# Microcontroller.net
KiCad netlist of a schematic drawn in Altium Designer
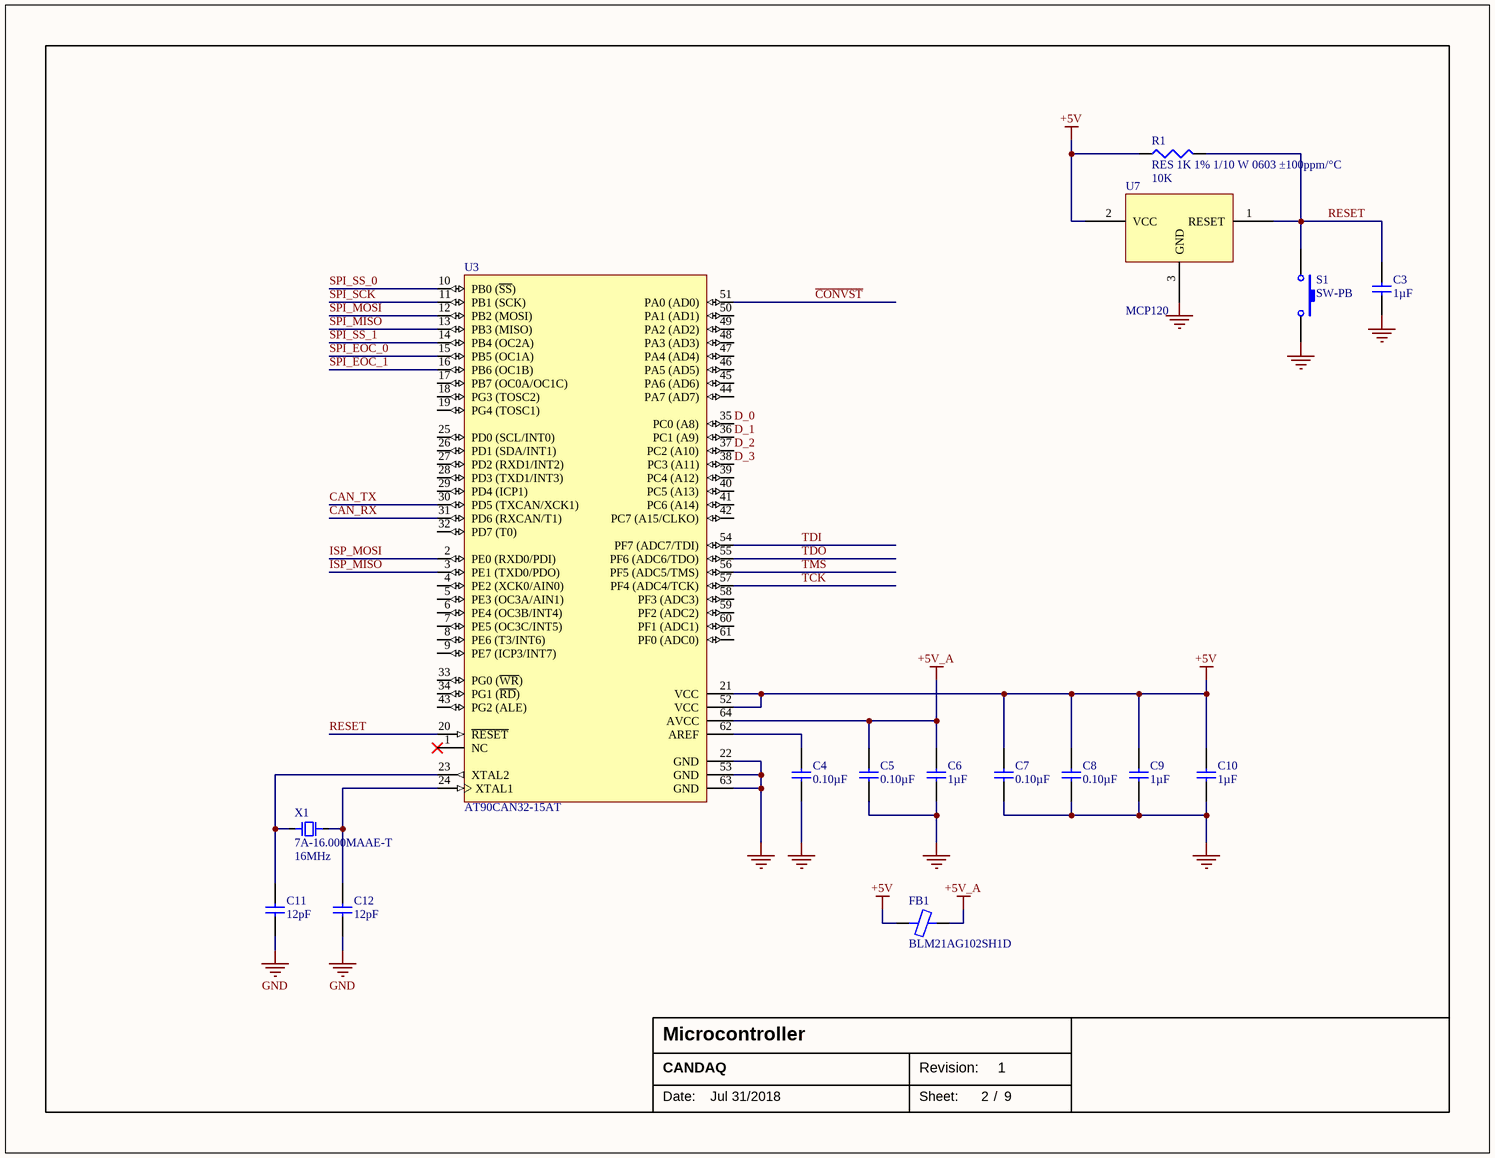
[diagram p0: Microcontroller.SchDoc]

(export (version "E")
  (design (tool "Eeschema 10.0.6"))
  (components
    (comp (ref "C3")
      (value "1µF")
      (footprint "1206")
      (fields
        (field (name "PART NUMBER") "CC0805KKX7R7BB105")
        (field (name "TOLERANCE") "±10%")
        (field (name "VOLTAGE") "16V")
      )
      (libsource (lib "Capacitors") (part "Capacitor"))
    )
    (comp (ref "C4")
      (value "0.10µF")
      (footprint "1206")
      (fields
        (field (name "PART NUMBER") "CC0402KRX7R7BB104")
        (field (name "TOLERANCE") "±10%")
        (field (name "VOLTAGE") "16V")
      )
      (libsource (lib "Capacitors") (part "Capacitor"))
    )
    (comp (ref "C5")
      (value "0.10µF")
      (footprint "1206")
      (fields
        (field (name "PART NUMBER") "CC0402KRX7R7BB104")
        (field (name "TOLERANCE") "±10%")
        (field (name "VOLTAGE") "16V")
      )
      (libsource (lib "Capacitors") (part "Capacitor"))
    )
    (comp (ref "C6")
      (value "1µF")
      (footprint "1206")
      (fields
        (field (name "PART NUMBER") "CC0805KKX7R7BB105")
        (field (name "TOLERANCE") "±10%")
        (field (name "VOLTAGE") "16V")
      )
      (libsource (lib "Capacitors") (part "Capacitor"))
    )
    (comp (ref "C7")
      (value "0.10µF")
      (footprint "1206")
      (fields
        (field (name "PART NUMBER") "CC0402KRX7R7BB104")
        (field (name "TOLERANCE") "±10%")
        (field (name "VOLTAGE") "16V")
      )
      (libsource (lib "Capacitors") (part "Capacitor"))
    )
    (comp (ref "C8")
      (value "0.10µF")
      (footprint "1206")
      (fields
        (field (name "PART NUMBER") "CC0402KRX7R7BB104")
        (field (name "TOLERANCE") "±10%")
        (field (name "VOLTAGE") "16V")
      )
      (libsource (lib "Capacitors") (part "Capacitor"))
    )
    (comp (ref "C9")
      (value "1µF")
      (footprint "1206")
      (fields
        (field (name "PART NUMBER") "CC0805KKX7R7BB105")
        (field (name "TOLERANCE") "±10%")
        (field (name "VOLTAGE") "16V")
      )
      (libsource (lib "Capacitors") (part "Capacitor"))
    )
    (comp (ref "C10")
      (value "1µF")
      (footprint "1206")
      (fields
        (field (name "PART NUMBER") "CC0805KKX7R7BB105")
        (field (name "TOLERANCE") "±10%")
        (field (name "VOLTAGE") "16V")
      )
      (libsource (lib "Capacitors") (part "Capacitor"))
    )
    (comp (ref "C11")
      (value "12pF")
      (footprint "1206")
      (fields
        (field (name "PART NUMBER") "CC0402JRNPO9BN120")
        (field (name "TOLERANCE") "±5%")
        (field (name "VOLTAGE") "50V")
      )
      (libsource (lib "Capacitors") (part "Capacitor"))
    )
    (comp (ref "C12")
      (value "12pF")
      (footprint "1206")
      (fields
        (field (name "PART NUMBER") "CC0402JRNPO9BN120")
        (field (name "TOLERANCE") "±5%")
        (field (name "VOLTAGE") "50V")
      )
      (libsource (lib "Capacitors") (part "Capacitor"))
    )
    (comp (ref "FB1")
      (value "BLM21AG102SH1D")
      (footprint "INDC2012X11N")
      (libsource (lib "PDU-UV17") (part "BLM21AG102SH1D"))
    )
    (comp (ref "R1")
      (value "RES 1K 1% 1/10 W 0603 ±100ppm/°C")
      (footprint "1206")
      (description "Resistor")
      (fields (field (name "ALTIUM_VALUE") "10K") (field (name "PUBLISHER") "Altium Limited"))
      (libsource (lib "Miscellaneous Devices") (part "Res3"))
    )
    (comp (ref "S1")
      (value "SW-PB")
      (footprint "Switch")
      (description "Switch")
      (fields (field (name "PUBLISHER") "Altium Limited"))
      (libsource (lib "Miscellaneous Devices") (part "SW-PB"))
    )
    (comp (ref "U3")
      (value "AT90CAN32-15AT")
      (footprint "TQFP80P1600X1600X120-64N")
      (libsource (lib "PDU-UV17") (part "AT90CAN32-15AT"))
    )
    (comp (ref "U7") (value "MCP120") (footprint "MCP120") (libsource (lib "CANDAQ") (part "MCP120")))
    (comp (ref "X1")
      (value "7A-16.000MAAE-T")
      (footprint "QFN200P500X320X135-2N")
      (description "SMD Crystal Oscillator 12 pF")
      (fields (field (name "ALTIUM_VALUE") "16MHz"))
      (libsource (lib "PDUv2") (part "7A-16.000MAAE-T"))
    )
  )
  (nets
    (net (code "1") (name "+5V") (class "Default")
      (node (ref "C10") (pin "1") (pinfunction "1_1") (pintype "passive"))
      (node (ref "C7") (pin "2") (pinfunction "2_2") (pintype "passive"))
      (node (ref "C8") (pin "2") (pinfunction "2_2") (pintype "passive"))
      (node (ref "C9") (pin "1") (pinfunction "1_1") (pintype "passive"))
      (node (ref "FB1") (pin "1") (pinfunction "1_1") (pintype "passive"))
      (node (ref "R1") (pin "1") (pinfunction "1_1") (pintype "passive"))
      (node (ref "U3") (pin "21") (pinfunction "VCC_21") (pintype "power_in"))
      (node (ref "U3") (pin "52") (pinfunction "VCC_52") (pintype "power_in"))
      (node (ref "U7") (pin "2") (pinfunction "VCC_2") (pintype "passive"))
    )
    (net (code "2") (name "+5V_A") (class "Default")
      (node (ref "C5") (pin "2") (pinfunction "2_2") (pintype "passive"))
      (node (ref "C6") (pin "1") (pinfunction "1_1") (pintype "passive"))
      (node (ref "FB1") (pin "2") (pinfunction "2_2") (pintype "passive"))
      (node (ref "U3") (pin "64") (pinfunction "AVCC_64") (pintype "power_in"))
    )
    (net (code "3") (name "/CAN_RX") (class "Default")
      (node (ref "U3") (pin "31") (pinfunction "PD6_(RXCAN/T1)_31") (pintype "bidirectional"))
    )
    (net (code "4") (name "/CAN_TX") (class "Default")
      (node (ref "U3") (pin "30") (pinfunction "PD5_(TXCAN/XCK1)_30") (pintype "bidirectional"))
    )
    (net (code "5") (name "/D_0") (class "Default")
      (node (ref "U3") (pin "35") (pinfunction "PC0_(A8)_35") (pintype "bidirectional"))
    )
    (net (code "6") (name "/D_1") (class "Default")
      (node (ref "U3") (pin "36") (pinfunction "PC1_(A9)_36") (pintype "bidirectional"))
    )
    (net (code "7") (name "/D_2") (class "Default")
      (node (ref "U3") (pin "37") (pinfunction "PC2_(A10)_37") (pintype "bidirectional"))
    )
    (net (code "8") (name "/D_3") (class "Default")
      (node (ref "U3") (pin "38") (pinfunction "PC3_(A11)_38") (pintype "bidirectional"))
    )
    (net (code "9") (name "/ISP_MISO") (class "Default")
      (node (ref "U3") (pin "3") (pinfunction "PE1_(TXD0/PDO)_3") (pintype "bidirectional"))
    )
    (net (code "10") (name "/ISP_MOSI") (class "Default")
      (node (ref "U3") (pin "2") (pinfunction "PE0_(RXD0/PDI)_2") (pintype "bidirectional"))
    )
    (net (code "11") (name "/RESET") (class "Default")
      (node (ref "C3") (pin "1") (pinfunction "1_1") (pintype "passive"))
      (node (ref "R1") (pin "2") (pinfunction "2_2") (pintype "passive"))
      (node (ref "S1") (pin "1") (pinfunction "1_1") (pintype "passive"))
      (node (ref "U3") (pin "20") (pinfunction "~{RESET}_20") (pintype "input"))
      (node (ref "U7") (pin "1") (pinfunction "RESET_1") (pintype "passive"))
    )
    (net (code "12") (name "/SPI_EOC_0") (class "Default")
      (node (ref "U3") (pin "15") (pinfunction "PB5_(OC1A)_15") (pintype "bidirectional"))
    )
    (net (code "13") (name "/SPI_EOC_1") (class "Default")
      (node (ref "U3") (pin "16") (pinfunction "PB6_(OC1B)_16") (pintype "bidirectional"))
    )
    (net (code "14") (name "/SPI_MISO") (class "Default")
      (node (ref "U3") (pin "13") (pinfunction "PB3_(MISO)_13") (pintype "bidirectional"))
    )
    (net (code "15") (name "/SPI_MOSI") (class "Default")
      (node (ref "U3") (pin "12") (pinfunction "PB2_(MOSI)_12") (pintype "bidirectional"))
    )
    (net (code "16") (name "/SPI_SCK") (class "Default")
      (node (ref "U3") (pin "11") (pinfunction "PB1_(SCK)_11") (pintype "bidirectional"))
    )
    (net (code "17") (name "/SPI_SS_0") (class "Default")
      (node (ref "U3") (pin "10") (pinfunction "PB0_(~{SS})_10") (pintype "bidirectional"))
    )
    (net (code "18") (name "/SPI_SS_1") (class "Default")
      (node (ref "U3") (pin "14") (pinfunction "PB4_(OC2A)_14") (pintype "bidirectional"))
    )
    (net (code "19") (name "/TCK") (class "Default")
      (node (ref "U3") (pin "57") (pinfunction "PF4_(ADC4/TCK)_57") (pintype "bidirectional"))
    )
    (net (code "20") (name "/TDI") (class "Default")
      (node (ref "U3") (pin "54") (pinfunction "PF7_(ADC7/TDI)_54") (pintype "bidirectional"))
    )
    (net (code "21") (name "/TDO") (class "Default")
      (node (ref "U3") (pin "55") (pinfunction "PF6_(ADC6/TDO)_55") (pintype "bidirectional"))
    )
    (net (code "22") (name "/TMS") (class "Default")
      (node (ref "U3") (pin "56") (pinfunction "PF5_(ADC5/TMS)_56") (pintype "bidirectional"))
    )
    (net (code "23") (name "/~{CONVST}") (class "Default")
      (node (ref "U3") (pin "51") (pinfunction "PA0_(AD0)_51") (pintype "bidirectional"))
    )
    (net (code "24") (name "GND") (class "Default")
      (node (ref "C10") (pin "2") (pinfunction "2_2") (pintype "passive"))
      (node (ref "C11") (pin "1") (pinfunction "1_1") (pintype "passive"))
      (node (ref "C12") (pin "1") (pinfunction "1_1") (pintype "passive"))
      (node (ref "C3") (pin "2") (pinfunction "2_2") (pintype "passive"))
      (node (ref "C4") (pin "1") (pinfunction "1_1") (pintype "passive"))
      (node (ref "C5") (pin "1") (pinfunction "1_1") (pintype "passive"))
      (node (ref "C6") (pin "2") (pinfunction "2_2") (pintype "passive"))
      (node (ref "C7") (pin "1") (pinfunction "1_1") (pintype "passive"))
      (node (ref "C8") (pin "1") (pinfunction "1_1") (pintype "passive"))
      (node (ref "C9") (pin "2") (pinfunction "2_2") (pintype "passive"))
      (node (ref "S1") (pin "2") (pinfunction "2_2") (pintype "passive"))
      (node (ref "U3") (pin "22") (pinfunction "GND_22") (pintype "power_in"))
      (node (ref "U3") (pin "53") (pinfunction "GND_53") (pintype "power_in"))
      (node (ref "U3") (pin "63") (pinfunction "GND_63") (pintype "power_in"))
      (node (ref "U7") (pin "3") (pinfunction "GND_3") (pintype "passive"))
    )
    (net (code "25") (name "Net-(U3-AREF)") (class "Default")
      (node (ref "C4") (pin "2") (pinfunction "2_2") (pintype "passive"))
      (node (ref "U3") (pin "62") (pinfunction "AREF_62") (pintype "power_in"))
    )
    (net (code "26") (name "Net-(U3-XTAL1)") (class "Default")
      (node (ref "C12") (pin "2") (pinfunction "2_2") (pintype "passive"))
      (node (ref "U3") (pin "24") (pinfunction "XTAL1_24") (pintype "input"))
      (node (ref "X1") (pin "2") (pinfunction "2_2") (pintype "passive"))
    )
    (net (code "27") (name "Net-(U3-XTAL2)") (class "Default")
      (node (ref "C11") (pin "2") (pinfunction "2_2") (pintype "passive"))
      (node (ref "U3") (pin "23") (pinfunction "XTAL2_23") (pintype "output"))
      (node (ref "X1") (pin "1") (pinfunction "1_1") (pintype "passive"))
    )
    (net (code "28") (name "unconnected-(U3-NC-Pad1)") (class "Default")
      (node (ref "U3") (pin "1") (pinfunction "NC_1") (pintype "passive+no_connect"))
    )
    (net (code "29") (name "unconnected-(U3-PA1_(AD1)-Pad50)") (class "Default")
      (node (ref "U3") (pin "50") (pinfunction "PA1_(AD1)_50") (pintype "bidirectional"))
    )
    (net (code "30") (name "unconnected-(U3-PA2_(AD2)-Pad49)") (class "Default")
      (node (ref "U3") (pin "49") (pinfunction "PA2_(AD2)_49") (pintype "bidirectional"))
    )
    (net (code "31") (name "unconnected-(U3-PA3_(AD3)-Pad48)") (class "Default")
      (node (ref "U3") (pin "48") (pinfunction "PA3_(AD3)_48") (pintype "bidirectional"))
    )
    (net (code "32") (name "unconnected-(U3-PA4_(AD4)-Pad47)") (class "Default")
      (node (ref "U3") (pin "47") (pinfunction "PA4_(AD4)_47") (pintype "bidirectional"))
    )
    (net (code "33") (name "unconnected-(U3-PA5_(AD5)-Pad46)") (class "Default")
      (node (ref "U3") (pin "46") (pinfunction "PA5_(AD5)_46") (pintype "bidirectional"))
    )
    (net (code "34") (name "unconnected-(U3-PA6_(AD6)-Pad45)") (class "Default")
      (node (ref "U3") (pin "45") (pinfunction "PA6_(AD6)_45") (pintype "bidirectional"))
    )
    (net (code "35") (name "unconnected-(U3-PA7_(AD7)-Pad44)") (class "Default")
      (node (ref "U3") (pin "44") (pinfunction "PA7_(AD7)_44") (pintype "bidirectional"))
    )
    (net (code "36") (name "unconnected-(U3-PB7_(OC0A{slash}OC1C)-Pad17)") (class "Default")
      (node (ref "U3") (pin "17") (pinfunction "PB7_(OC0A/OC1C)_17") (pintype "bidirectional"))
    )
    (net (code "37") (name "unconnected-(U3-PC4_(A12)-Pad39)") (class "Default")
      (node (ref "U3") (pin "39") (pinfunction "PC4_(A12)_39") (pintype "bidirectional"))
    )
    (net (code "38") (name "unconnected-(U3-PC5_(A13)-Pad40)") (class "Default")
      (node (ref "U3") (pin "40") (pinfunction "PC5_(A13)_40") (pintype "bidirectional"))
    )
    (net (code "39") (name "unconnected-(U3-PC6_(A14)-Pad41)") (class "Default")
      (node (ref "U3") (pin "41") (pinfunction "PC6_(A14)_41") (pintype "bidirectional"))
    )
    (net (code "40") (name "unconnected-(U3-PC7_(A15{slash}CLKO)-Pad42)") (class "Default")
      (node (ref "U3") (pin "42") (pinfunction "PC7_(A15/CLKO)_42") (pintype "bidirectional"))
    )
    (net (code "41") (name "unconnected-(U3-PD0_(SCL{slash}INT0)-Pad25)") (class "Default")
      (node (ref "U3") (pin "25") (pinfunction "PD0_(SCL/INT0)_25") (pintype "bidirectional"))
    )
    (net (code "42") (name "unconnected-(U3-PD1_(SDA{slash}INT1)-Pad26)") (class "Default")
      (node (ref "U3") (pin "26") (pinfunction "PD1_(SDA/INT1)_26") (pintype "bidirectional"))
    )
    (net (code "43") (name "unconnected-(U3-PD2_(RXD1{slash}INT2)-Pad27)") (class "Default")
      (node (ref "U3") (pin "27") (pinfunction "PD2_(RXD1/INT2)_27") (pintype "bidirectional"))
    )
    (net (code "44") (name "unconnected-(U3-PD3_(TXD1{slash}INT3)-Pad28)") (class "Default")
      (node (ref "U3") (pin "28") (pinfunction "PD3_(TXD1/INT3)_28") (pintype "bidirectional"))
    )
    (net (code "45") (name "unconnected-(U3-PD4_(ICP1)-Pad29)") (class "Default")
      (node (ref "U3") (pin "29") (pinfunction "PD4_(ICP1)_29") (pintype "bidirectional"))
    )
    (net (code "46") (name "unconnected-(U3-PD7_(T0)-Pad32)") (class "Default")
      (node (ref "U3") (pin "32") (pinfunction "PD7_(T0)_32") (pintype "bidirectional"))
    )
    (net (code "47") (name "unconnected-(U3-PE2_(XCK0{slash}AIN0)-Pad4)") (class "Default")
      (node (ref "U3") (pin "4") (pinfunction "PE2_(XCK0/AIN0)_4") (pintype "bidirectional"))
    )
    (net (code "48") (name "unconnected-(U3-PE3_(OC3A{slash}AIN1)-Pad5)") (class "Default")
      (node (ref "U3") (pin "5") (pinfunction "PE3_(OC3A/AIN1)_5") (pintype "bidirectional"))
    )
    (net (code "49") (name "unconnected-(U3-PE4_(OC3B{slash}INT4)-Pad6)") (class "Default")
      (node (ref "U3") (pin "6") (pinfunction "PE4_(OC3B/INT4)_6") (pintype "bidirectional"))
    )
    (net (code "50") (name "unconnected-(U3-PE5_(OC3C{slash}INT5)-Pad7)") (class "Default")
      (node (ref "U3") (pin "7") (pinfunction "PE5_(OC3C/INT5)_7") (pintype "bidirectional"))
    )
    (net (code "51") (name "unconnected-(U3-PE6_(T3{slash}INT6)-Pad8)") (class "Default")
      (node (ref "U3") (pin "8") (pinfunction "PE6_(T3/INT6)_8") (pintype "bidirectional"))
    )
    (net (code "52") (name "unconnected-(U3-PE7_(ICP3{slash}INT7)-Pad9)") (class "Default")
      (node (ref "U3") (pin "9") (pinfunction "PE7_(ICP3/INT7)_9") (pintype "bidirectional"))
    )
    (net (code "53") (name "unconnected-(U3-PF0_(ADC0)-Pad61)") (class "Default")
      (node (ref "U3") (pin "61") (pinfunction "PF0_(ADC0)_61") (pintype "bidirectional"))
    )
    (net (code "54") (name "unconnected-(U3-PF1_(ADC1)-Pad60)") (class "Default")
      (node (ref "U3") (pin "60") (pinfunction "PF1_(ADC1)_60") (pintype "bidirectional"))
    )
    (net (code "55") (name "unconnected-(U3-PF2_(ADC2)-Pad59)") (class "Default")
      (node (ref "U3") (pin "59") (pinfunction "PF2_(ADC2)_59") (pintype "bidirectional"))
    )
    (net (code "56") (name "unconnected-(U3-PF3_(ADC3)-Pad58)") (class "Default")
      (node (ref "U3") (pin "58") (pinfunction "PF3_(ADC3)_58") (pintype "bidirectional"))
    )
    (net (code "57") (name "unconnected-(U3-PG0_(~{WR})-Pad33)") (class "Default")
      (node (ref "U3") (pin "33") (pinfunction "PG0_(~{WR})_33") (pintype "bidirectional"))
    )
    (net (code "58") (name "unconnected-(U3-PG1_(~{RD})-Pad34)") (class "Default")
      (node (ref "U3") (pin "34") (pinfunction "PG1_(~{RD})_34") (pintype "bidirectional"))
    )
    (net (code "59") (name "unconnected-(U3-PG2_(ALE)-Pad43)") (class "Default")
      (node (ref "U3") (pin "43") (pinfunction "PG2_(ALE)_43") (pintype "bidirectional"))
    )
    (net (code "60") (name "unconnected-(U3-PG3_(TOSC2)-Pad18)") (class "Default")
      (node (ref "U3") (pin "18") (pinfunction "PG3_(TOSC2)_18") (pintype "bidirectional"))
    )
    (net (code "61") (name "unconnected-(U3-PG4_(TOSC1)-Pad19)") (class "Default")
      (node (ref "U3") (pin "19") (pinfunction "PG4_(TOSC1)_19") (pintype "bidirectional"))
    )
  )
)
